# PotBoard.net
KiCad netlist of a schematic drawn in EAGLE
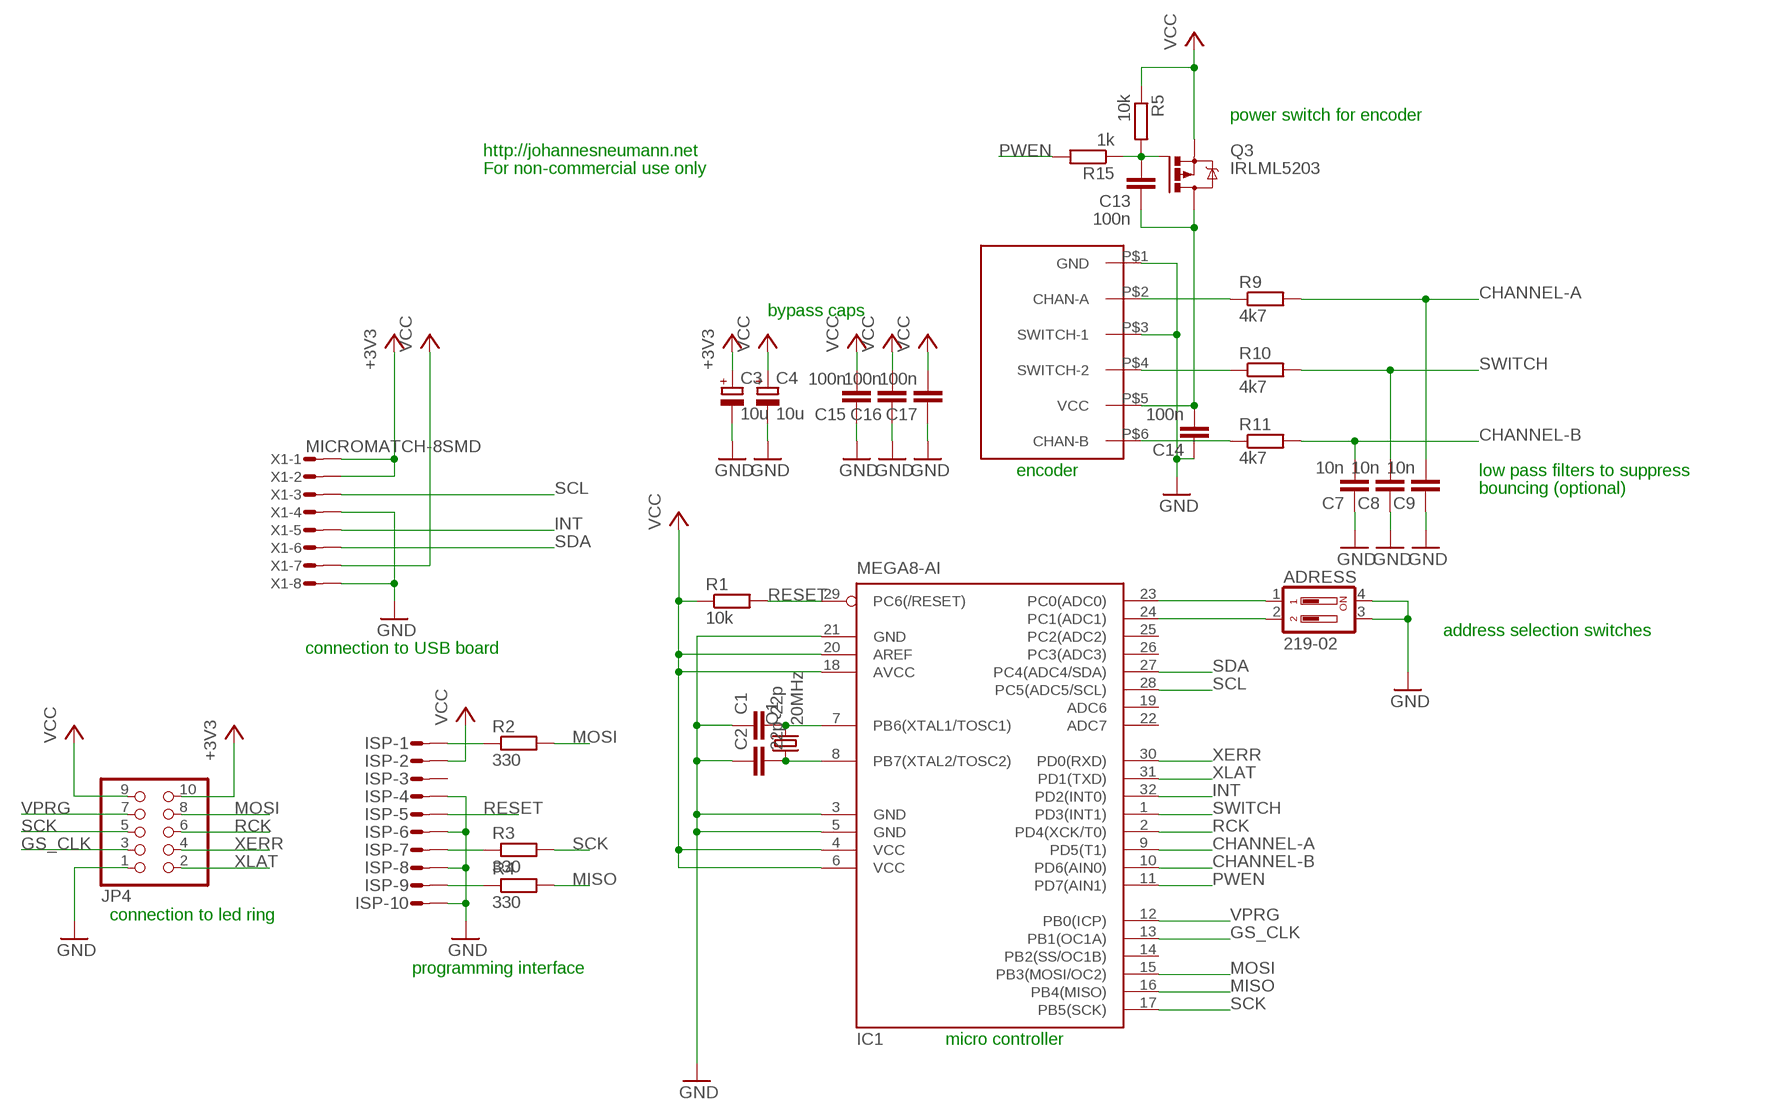
[diagram p0: schematic, sheet 1]

(export (version "E")
  (design (tool "Eeschema 10.0.6"))
  (components
    (comp (ref "ADRESS")
      (value "219-02")
      (footprint "eagle-import:CTS-219-02")
      (libsource (lib "eagle-import") (part "219-02"))
    )
    (comp (ref "C1")
      (value "22p")
      (footprint "eagle-import:C0603")
      (libsource (lib "eagle-import") (part "C-EUC0603"))
    )
    (comp (ref "C2")
      (value "22p")
      (footprint "eagle-import:C0603")
      (libsource (lib "eagle-import") (part "C-EUC0603"))
    )
    (comp (ref "C3")
      (value "10u")
      (footprint "eagle-import:153CLV-0505")
      (libsource (lib "eagle-import") (part "CPOL-EU153CLV-0505"))
    )
    (comp (ref "C4")
      (value "10u")
      (footprint "eagle-import:153CLV-0505")
      (libsource (lib "eagle-import") (part "CPOL-EU153CLV-0505"))
    )
    (comp (ref "C7")
      (value "10n")
      (footprint "eagle-import:C0603")
      (libsource (lib "eagle-import") (part "C-EUC0603"))
    )
    (comp (ref "C8")
      (value "10n")
      (footprint "eagle-import:C0603")
      (libsource (lib "eagle-import") (part "C-EUC0603"))
    )
    (comp (ref "C9")
      (value "10n")
      (footprint "eagle-import:C0603")
      (libsource (lib "eagle-import") (part "C-EUC0603"))
    )
    (comp (ref "C13")
      (value "100n")
      (footprint "eagle-import:C0603")
      (libsource (lib "eagle-import") (part "C-EUC0603"))
    )
    (comp (ref "C14")
      (value "100n")
      (footprint "eagle-import:C0603")
      (libsource (lib "eagle-import") (part "C-EUC0603"))
    )
    (comp (ref "C15")
      (value "100n")
      (footprint "eagle-import:C0603")
      (libsource (lib "eagle-import") (part "C-EUC0603"))
    )
    (comp (ref "C16")
      (value "100n")
      (footprint "eagle-import:C0603")
      (libsource (lib "eagle-import") (part "C-EUC0603"))
    )
    (comp (ref "C17")
      (value "100n")
      (footprint "eagle-import:C0603")
      (libsource (lib "eagle-import") (part "C-EUC0603"))
    )
    (comp (ref "IC1")
      (value "MEGA8-AI")
      (footprint "eagle-import:TQFP32-08")
      (libsource (lib "eagle-import") (part "MEGA8-AI"))
    )
    (comp (ref "ISP")
      (value "MICROMATCH-10-SMD")
      (footprint "eagle-import:MICROMATCH-10-SMD")
      (libsource (lib "eagle-import") (part "MICROMATCH-10-SMD"))
    )
    (comp (ref "JP4")
      (value "PINHD-2X5_2.54-SMD")
      (footprint "eagle-import:2X05SMD")
      (libsource (lib "eagle-import") (part "PINHD-2X5_2.54-SMD"))
    )
    (comp (ref "Q1")
      (value "20MHz")
      (footprint "eagle-import:SM49")
      (libsource (lib "eagle-import") (part "CRYSTALSM49"))
    )
    (comp (ref "Q3")
      (value "IRLML5203")
      (footprint "eagle-import:MICRO3")
      (libsource (lib "eagle-import") (part "IRLML5203"))
    )
    (comp (ref "R1")
      (value "10k")
      (footprint "eagle-import:R0603")
      (libsource (lib "eagle-import") (part "R-EU_R0603"))
    )
    (comp (ref "R2")
      (value "330")
      (footprint "eagle-import:R0603")
      (libsource (lib "eagle-import") (part "R-EU_R0603"))
    )
    (comp (ref "R3")
      (value "330")
      (footprint "eagle-import:R0603")
      (libsource (lib "eagle-import") (part "R-EU_R0603"))
    )
    (comp (ref "R4")
      (value "330")
      (footprint "eagle-import:R0603")
      (libsource (lib "eagle-import") (part "R-EU_R0603"))
    )
    (comp (ref "R5")
      (value "10k")
      (footprint "eagle-import:R0603")
      (libsource (lib "eagle-import") (part "R-EU_R0603"))
    )
    (comp (ref "R9")
      (value "4k7")
      (footprint "eagle-import:R0603")
      (libsource (lib "eagle-import") (part "R-EU_R0603"))
    )
    (comp (ref "R10")
      (value "4k7")
      (footprint "eagle-import:R0603")
      (libsource (lib "eagle-import") (part "R-EU_R0603"))
    )
    (comp (ref "R11")
      (value "4k7")
      (footprint "eagle-import:R0603")
      (libsource (lib "eagle-import") (part "R-EU_R0603"))
    )
    (comp (ref "R15")
      (value "1k")
      (footprint "eagle-import:R0603")
      (libsource (lib "eagle-import") (part "R-EU_R0603"))
    )
    (comp (ref "U$1")
      (value "BOURNS_EM14")
      (footprint "eagle-import:BOURNS_EM14_AXIAL")
      (libsource (lib "eagle-import") (part "BOURNS_EM14"))
    )
    (comp (ref "X1")
      (value "MICROMATCH-8SMD")
      (footprint "eagle-import:MICROMATCH-8-SMD")
      (libsource (lib "eagle-import") (part "MICROMATCH-8SMD"))
    )
  )
  (nets
    (net (code "1") (name "+3V3") (class "Default")
      (node (ref "C3") (pin "+") (pinfunction "+_+") (pintype "passive"))
      (node (ref "JP4") (pin "10") (pinfunction "10_10") (pintype "passive"))
      (node (ref "X1") (pin "1") (pinfunction "S_1") (pintype "passive"))
      (node (ref "X1") (pin "2") (pinfunction "S_2") (pintype "passive"))
    )
    (net (code "2") (name "/CHANNEL-A") (class "Default")
      (node (ref "C9") (pin "2") (pinfunction "2_2") (pintype "passive"))
      (node (ref "IC1") (pin "9") (pinfunction "PD5(T1)_9") (pintype "bidirectional"))
      (node (ref "R9") (pin "2") (pinfunction "2_2") (pintype "passive"))
    )
    (net (code "3") (name "/CHANNEL-B") (class "Default")
      (node (ref "C7") (pin "2") (pinfunction "2_2") (pintype "passive"))
      (node (ref "IC1") (pin "10") (pinfunction "PD6(AIN0)_10") (pintype "bidirectional"))
      (node (ref "R11") (pin "2") (pinfunction "2_2") (pintype "passive"))
    )
    (net (code "4") (name "/GS_CLK") (class "Default")
      (node (ref "IC1") (pin "13") (pinfunction "PB1(OC1A)_13") (pintype "bidirectional"))
      (node (ref "JP4") (pin "3") (pinfunction "3_3") (pintype "passive"))
    )
    (net (code "5") (name "/INT") (class "Default")
      (node (ref "IC1") (pin "32") (pinfunction "PD2(INT0)_32") (pintype "bidirectional"))
      (node (ref "X1") (pin "5") (pinfunction "S_5") (pintype "passive"))
    )
    (net (code "6") (name "/MISO") (class "Default")
      (node (ref "IC1") (pin "16") (pinfunction "PB4(MISO)_16") (pintype "bidirectional"))
      (node (ref "R4") (pin "2") (pinfunction "2_2") (pintype "passive"))
    )
    (net (code "7") (name "/MOSI") (class "Default")
      (node (ref "IC1") (pin "15") (pinfunction "PB3(MOSI/OC2)_15") (pintype "bidirectional"))
      (node (ref "JP4") (pin "8") (pinfunction "8_8") (pintype "passive"))
      (node (ref "R2") (pin "2") (pinfunction "2_2") (pintype "passive"))
    )
    (net (code "8") (name "/PWEN") (class "Default")
      (node (ref "IC1") (pin "11") (pinfunction "PD7(AIN1)_11") (pintype "bidirectional"))
      (node (ref "R15") (pin "2") (pinfunction "2_2") (pintype "passive"))
    )
    (net (code "9") (name "/RCK") (class "Default")
      (node (ref "IC1") (pin "2") (pinfunction "PD4(XCK/T0)_2") (pintype "bidirectional"))
      (node (ref "JP4") (pin "6") (pinfunction "6_6") (pintype "passive"))
    )
    (net (code "10") (name "/RESET") (class "Default")
      (node (ref "IC1") (pin "29") (pinfunction "PC6(/RESET)_29") (pintype "bidirectional"))
      (node (ref "ISP") (pin "P$5") (pinfunction "S_P$5") (pintype "passive"))
      (node (ref "R1") (pin "2") (pinfunction "2_2") (pintype "passive"))
    )
    (net (code "11") (name "/SCK") (class "Default")
      (node (ref "IC1") (pin "17") (pinfunction "PB5(SCK)_17") (pintype "bidirectional"))
      (node (ref "JP4") (pin "5") (pinfunction "5_5") (pintype "passive"))
      (node (ref "R3") (pin "2") (pinfunction "2_2") (pintype "passive"))
    )
    (net (code "12") (name "/SCL") (class "Default")
      (node (ref "IC1") (pin "28") (pinfunction "PC5(ADC5/SCL)_28") (pintype "bidirectional"))
      (node (ref "X1") (pin "3") (pinfunction "S_3") (pintype "passive"))
    )
    (net (code "13") (name "/SDA") (class "Default")
      (node (ref "IC1") (pin "27") (pinfunction "PC4(ADC4/SDA)_27") (pintype "bidirectional"))
      (node (ref "X1") (pin "6") (pinfunction "S_6") (pintype "passive"))
    )
    (net (code "14") (name "/SWITCH") (class "Default")
      (node (ref "C8") (pin "2") (pinfunction "2_2") (pintype "passive"))
      (node (ref "IC1") (pin "1") (pinfunction "PD3(INT1)_1") (pintype "bidirectional"))
      (node (ref "R10") (pin "2") (pinfunction "2_2") (pintype "passive"))
    )
    (net (code "15") (name "/VPRG") (class "Default")
      (node (ref "IC1") (pin "12") (pinfunction "PB0(ICP)_12") (pintype "bidirectional"))
      (node (ref "JP4") (pin "7") (pinfunction "7_7") (pintype "passive"))
    )
    (net (code "16") (name "/XERR") (class "Default")
      (node (ref "IC1") (pin "30") (pinfunction "PD0(RXD)_30") (pintype "bidirectional"))
      (node (ref "JP4") (pin "4") (pinfunction "4_4") (pintype "passive"))
    )
    (net (code "17") (name "/XLAT") (class "Default")
      (node (ref "IC1") (pin "31") (pinfunction "PD1(TXD)_31") (pintype "bidirectional"))
      (node (ref "JP4") (pin "2") (pinfunction "2_2") (pintype "passive"))
    )
    (net (code "18") (name "GND") (class "Default")
      (node (ref "ADRESS") (pin "3") (pinfunction "3_3") (pintype "passive"))
      (node (ref "ADRESS") (pin "4") (pinfunction "4_4") (pintype "passive"))
      (node (ref "C1") (pin "1") (pinfunction "1_1") (pintype "passive"))
      (node (ref "C14") (pin "1") (pinfunction "1_1") (pintype "passive"))
      (node (ref "C15") (pin "1") (pinfunction "1_1") (pintype "passive"))
      (node (ref "C16") (pin "1") (pinfunction "1_1") (pintype "passive"))
      (node (ref "C17") (pin "1") (pinfunction "1_1") (pintype "passive"))
      (node (ref "C2") (pin "1") (pinfunction "1_1") (pintype "passive"))
      (node (ref "C3") (pin "-") (pinfunction "-_-") (pintype "passive"))
      (node (ref "C4") (pin "-") (pinfunction "-_-") (pintype "passive"))
      (node (ref "C7") (pin "1") (pinfunction "1_1") (pintype "passive"))
      (node (ref "C8") (pin "1") (pinfunction "1_1") (pintype "passive"))
      (node (ref "C9") (pin "1") (pinfunction "1_1") (pintype "passive"))
      (node (ref "IC1") (pin "21") (pinfunction "GND_21") (pintype "power_in"))
      (node (ref "IC1") (pin "3") (pinfunction "GND_3") (pintype "power_in"))
      (node (ref "IC1") (pin "5") (pinfunction "GND_5") (pintype "power_in"))
      (node (ref "ISP") (pin "P$10") (pinfunction "S_P$10") (pintype "passive"))
      (node (ref "ISP") (pin "P$4") (pinfunction "S_P$4") (pintype "passive"))
      (node (ref "ISP") (pin "P$6") (pinfunction "S_P$6") (pintype "passive"))
      (node (ref "ISP") (pin "P$8") (pinfunction "S_P$8") (pintype "passive"))
      (node (ref "JP4") (pin "1") (pinfunction "1_1") (pintype "passive"))
      (node (ref "U$1") (pin "P$1") (pinfunction "GND_P$1") (pintype "bidirectional"))
      (node (ref "U$1") (pin "P$3") (pinfunction "SWITCH-1_P$3") (pintype "bidirectional"))
      (node (ref "X1") (pin "4") (pinfunction "S_4") (pintype "passive"))
      (node (ref "X1") (pin "8") (pinfunction "S_8") (pintype "passive"))
    )
    (net (code "19") (name "Net-(IC1-PB6(XTAL1{slash}TOSC1))") (class "Default")
      (node (ref "C1") (pin "2") (pinfunction "2_2") (pintype "passive"))
      (node (ref "IC1") (pin "7") (pinfunction "PB6(XTAL1/TOSC1)_7") (pintype "bidirectional"))
      (node (ref "Q1") (pin "2") (pinfunction "2_2") (pintype "passive"))
    )
    (net (code "20") (name "Net-(IC1-PB7(XTAL2{slash}TOSC2))") (class "Default")
      (node (ref "C2") (pin "2") (pinfunction "2_2") (pintype "passive"))
      (node (ref "IC1") (pin "8") (pinfunction "PB7(XTAL2/TOSC2)_8") (pintype "bidirectional"))
      (node (ref "Q1") (pin "1") (pinfunction "1_1") (pintype "passive"))
    )
    (net (code "21") (name "Net-(IC1-PC0(ADC0))") (class "Default")
      (node (ref "ADRESS") (pin "1") (pinfunction "1_1") (pintype "passive"))
      (node (ref "IC1") (pin "23") (pinfunction "PC0(ADC0)_23") (pintype "bidirectional"))
    )
    (net (code "22") (name "Net-(IC1-PC1(ADC1))") (class "Default")
      (node (ref "ADRESS") (pin "2") (pinfunction "2_2") (pintype "passive"))
      (node (ref "IC1") (pin "24") (pinfunction "PC1(ADC1)_24") (pintype "bidirectional"))
    )
    (net (code "23") (name "Net-(ISPA-S)") (class "Default")
      (node (ref "ISP") (pin "P$1") (pinfunction "S_P$1") (pintype "passive"))
      (node (ref "R2") (pin "1") (pinfunction "1_1") (pintype "passive"))
    )
    (net (code "24") (name "Net-(ISPH-S)") (class "Default")
      (node (ref "ISP") (pin "P$7") (pinfunction "S_P$7") (pintype "passive"))
      (node (ref "R3") (pin "1") (pinfunction "1_1") (pintype "passive"))
    )
    (net (code "25") (name "Net-(ISPJ-S)") (class "Default")
      (node (ref "ISP") (pin "P$9") (pinfunction "S_P$9") (pintype "passive"))
      (node (ref "R4") (pin "1") (pinfunction "1_1") (pintype "passive"))
    )
    (net (code "26") (name "Net-(Q3-D)") (class "Default")
      (node (ref "C13") (pin "1") (pinfunction "1_1") (pintype "passive"))
      (node (ref "C14") (pin "2") (pinfunction "2_2") (pintype "passive"))
      (node (ref "Q3") (pin "3") (pinfunction "D_3") (pintype "passive"))
      (node (ref "U$1") (pin "P$5") (pinfunction "VCC_P$5") (pintype "bidirectional"))
    )
    (net (code "27") (name "Net-(Q3-G)") (class "Default")
      (node (ref "C13") (pin "2") (pinfunction "2_2") (pintype "passive"))
      (node (ref "Q3") (pin "1") (pinfunction "G_1") (pintype "passive"))
      (node (ref "R15") (pin "1") (pinfunction "1_1") (pintype "passive"))
      (node (ref "R5") (pin "2") (pinfunction "2_2") (pintype "passive"))
    )
    (net (code "28") (name "Net-(U$1-CHAN-A)") (class "Default")
      (node (ref "R9") (pin "1") (pinfunction "1_1") (pintype "passive"))
      (node (ref "U$1") (pin "P$2") (pinfunction "CHAN-A_P$2") (pintype "bidirectional"))
    )
    (net (code "29") (name "Net-(U$1-CHAN-B)") (class "Default")
      (node (ref "R11") (pin "1") (pinfunction "1_1") (pintype "passive"))
      (node (ref "U$1") (pin "P$6") (pinfunction "CHAN-B_P$6") (pintype "bidirectional"))
    )
    (net (code "30") (name "Net-(U$1-SWITCH-2)") (class "Default")
      (node (ref "R10") (pin "1") (pinfunction "1_1") (pintype "passive"))
      (node (ref "U$1") (pin "P$4") (pinfunction "SWITCH-2_P$4") (pintype "bidirectional"))
    )
    (net (code "31") (name "VCC") (class "Default")
      (node (ref "C15") (pin "2") (pinfunction "2_2") (pintype "passive"))
      (node (ref "C16") (pin "2") (pinfunction "2_2") (pintype "passive"))
      (node (ref "C17") (pin "2") (pinfunction "2_2") (pintype "passive"))
      (node (ref "C4") (pin "+") (pinfunction "+_+") (pintype "passive"))
      (node (ref "IC1") (pin "18") (pinfunction "AVCC_18") (pintype "power_in"))
      (node (ref "IC1") (pin "20") (pinfunction "AREF_20") (pintype "passive"))
      (node (ref "IC1") (pin "4") (pinfunction "VCC_4") (pintype "power_in"))
      (node (ref "IC1") (pin "6") (pinfunction "VCC_6") (pintype "power_in"))
      (node (ref "ISP") (pin "P$2") (pinfunction "S_P$2") (pintype "passive"))
      (node (ref "JP4") (pin "9") (pinfunction "9_9") (pintype "passive"))
      (node (ref "Q3") (pin "2") (pinfunction "S_2") (pintype "passive"))
      (node (ref "R1") (pin "1") (pinfunction "1_1") (pintype "passive"))
      (node (ref "R5") (pin "1") (pinfunction "1_1") (pintype "passive"))
      (node (ref "X1") (pin "7") (pinfunction "S_7") (pintype "passive"))
    )
    (net (code "32") (name "unconnected-(IC1-ADC6-Pad19)") (class "Default")
      (node (ref "IC1") (pin "19") (pinfunction "ADC6_19") (pintype "bidirectional"))
    )
    (net (code "33") (name "unconnected-(IC1-ADC7-Pad22)") (class "Default")
      (node (ref "IC1") (pin "22") (pinfunction "ADC7_22") (pintype "bidirectional"))
    )
    (net (code "34") (name "unconnected-(IC1-PB2(SS{slash}OC1B)-Pad14)") (class "Default")
      (node (ref "IC1") (pin "14") (pinfunction "PB2(SS/OC1B)_14") (pintype "bidirectional"))
    )
    (net (code "35") (name "unconnected-(IC1-PC2(ADC2)-Pad25)") (class "Default")
      (node (ref "IC1") (pin "25") (pinfunction "PC2(ADC2)_25") (pintype "bidirectional"))
    )
    (net (code "36") (name "unconnected-(IC1-PC3(ADC3)-Pad26)") (class "Default")
      (node (ref "IC1") (pin "26") (pinfunction "PC3(ADC3)_26") (pintype "bidirectional"))
    )
    (net (code "37") (name "unconnected-(ISPD-S-PadP$3)") (class "Default")
      (node (ref "ISP") (pin "P$3") (pinfunction "S_P$3") (pintype "passive"))
    )
  )
)
